# fsm.net
KiCad netlist of a schematic drawn in Altium Designer
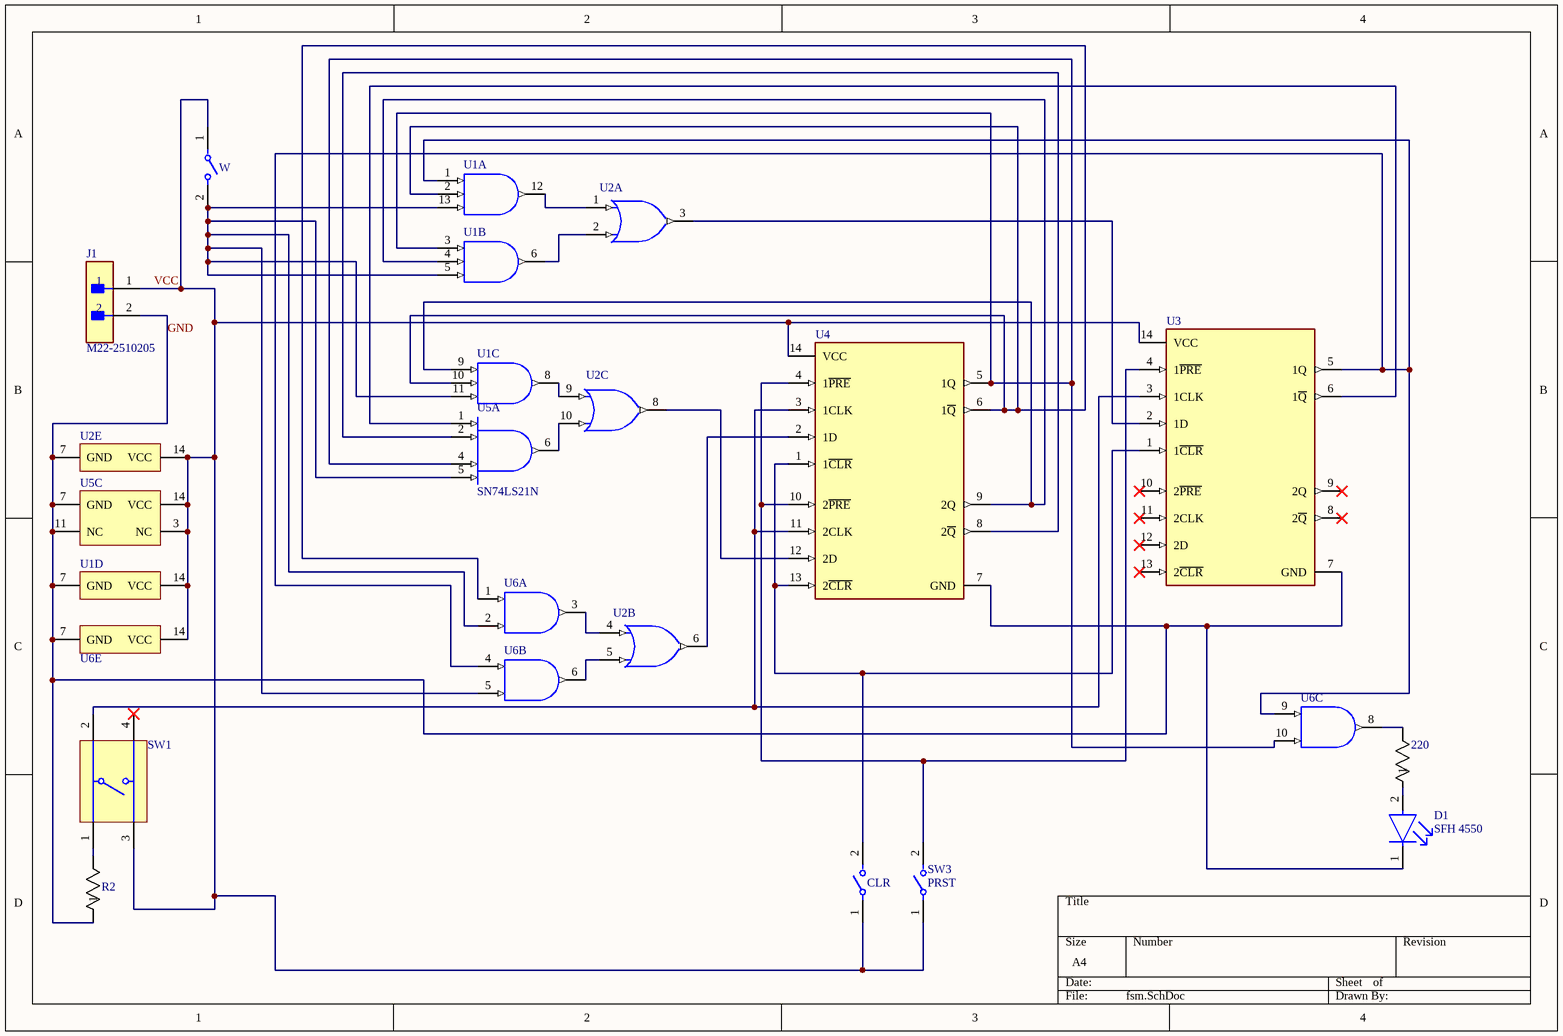
[diagram p0: fsm.SchDoc]

(export (version "E")
  (design (tool "Eeschema 10.0.6"))
  (components
    (comp (ref "220")
      (value "AC05000002200JAC00")
      (footprint "RES_AC05_VIS")
      (description "AC05000002200JAC00 Resistor, 220 Ohm, ± 5%, 5 W, Axial Leaded, Wirewound, General Purpose")
      (fields (field (name "TOLERANCE") "5%"))
      (libsource (lib "Altium Content Vault") (part "AC05000002200JAC00"))
    )
    (comp (ref "D1")
      (value "SFH 4550")
      (footprint "FP-SFH_4550-MFG")
      (description "EMITTER IR 860NM 100MA RADIAL")
      (fields
        (field (name "OCTOPART") "https://octopart.com/sfh+4550-osram+opto-55410894")
        (field (name "MANUFACTURER") "Osram Opto")
      )
      (libsource (lib "Altium Content Vault") (part "75a0115997dd6a71327e26aab64f6f8"))
    )
    (comp (ref "J1")
      (value "M22-2510205")
      (footprint "FP-M22-2510205-MFG")
      (description "CONN HEADER VERT 2POS 2MM")
      (fields
        (field (name "MANUFACTURER") "Harwin")
        (field (name "OCTOPART") "https://octopart.com/m22-2510205-harwin-2538221")
      )
      (libsource (lib "Altium Content Vault") (part "3bc925449376181038e59eaffc5286c"))
    )
    (comp (ref "R2")
      (value "AC03000001001JAC00")
      (footprint "RES_AC03_VIS")
      (description "AC03000001001JAC00 Resistor, 1 kOhm, ± 5%, 3 W, Axial Leaded, Wirewound, General Purpose")
      (fields (field (name "TOLERANCE") "5%"))
      (libsource (lib "Altium Content Vault") (part "AC03000001001JAC00"))
    )
    (comp (ref "SW1")
      (value "1825910-6")
      (footprint "TECO-1825910-6_V")
      (description "Tact Switch, SPST-NO, 0.05 A, -35 to 85 degC, 4-Pin THD, RoHS, Bulk")
      (fields (field (name "MANUFACTURER") "TE Connectivity"))
      (libsource (lib "Altium Content Vault") (part "SW-SPST-4_A"))
    )
    (comp (ref "SW2")
      (value "CLR")
      (footprint "FP-BD01-MFG")
      (description "SWITCH SLIDE DIP SPST 100MA 5V")
      (libsource (lib "Altium Content Vault") (part "bb27bde45df87f1f469753f287ef5ae"))
    )
    (comp (ref "SW3")
      (value "PRST")
      (footprint "FP-BD01-MFG")
      (description "SWITCH SLIDE DIP SPST 100MA 5V")
      (libsource (lib "Altium Content Vault") (part "bb27bde45df87f1f469753f287ef5ae"))
    )
    (comp (ref "U1")
      (value "SN74LS11N")
      (footprint "N0014A")
      (description "Triple 3-input positive-AND gates, N0014A, TUBE")
      (fields
        (field (name "MANUFACTURER") "Texas Instruments")
        (field (name "GENERIC PART NUMBER") "SN74LS11")
      )
      (libsource (lib "Altium Content Vault") (part "TI-AND-3-3IN-14"))
    )
    (comp (ref "U2")
      (value "SN74AHC32N")
      (footprint "N0014A")
      (description "Quadruple 2-Input Positive-OR Gates, N0014A, TUBE")
      (fields
        (field (name "MANUFACTURER") "Texas Instruments")
        (field (name "GENERIC PART NUMBER") "SN74AHC32")
      )
      (libsource (lib "Altium Content Vault") (part "TI-OR-4-2IN-14"))
    )
    (comp (ref "U3")
      (value "SN74HCT74N")
      (footprint "FP-N0014A-MFG")
      (description "IC FF D-TYPE DUAL 1BIT 14DIP")
      (libsource (lib "Altium Content Vault") (part "d9c658a62ce850adab6c7e3446338f7"))
    )
    (comp (ref "U4")
      (value "SN74HCT74N")
      (footprint "FP-N0014A-MFG")
      (description "IC FF D-TYPE DUAL 1BIT 14DIP")
      (libsource (lib "Altium Content Vault") (part "d9c658a62ce850adab6c7e3446338f7"))
    )
    (comp (ref "U5")
      (value "SN74LS21N")
      (footprint "N0014A")
      (description "Dual 4-input positive-AND gates, N0014A, TUBE")
      (fields
        (field (name "GENERIC PART NUMBER") "SN74LS21")
        (field (name "MANUFACTURER") "Texas Instruments")
      )
      (libsource (lib "") (part "TI-SNX4XXX21X-14_1"))
    )
    (comp (ref "U6")
      (value "SN74AC08N")
      (footprint "N0014A")
      (description "Quadruple 2-Input Positive-AND Gates, N0014A, TUBE")
      (fields
        (field (name "GENERIC PART NUMBER") "SN74AC08")
        (field (name "MANUFACTURER") "Texas Instruments")
      )
      (libsource (lib "Altium Content Vault") (part "TI-AND-4-2IN-14"))
    )
    (comp (ref "W")
      (value "BD01")
      (footprint "FP-BD01-MFG")
      (description "SWITCH SLIDE DIP SPST 100MA 5V")
      (libsource (lib "Altium Content Vault") (part "bb27bde45df87f1f469753f287ef5ae"))
    )
  )
  (nets
    (net (code "1") (name "/GND") (class "Default")
      (node (ref "D1") (pin "1") (pinfunction "C_1") (pintype "passive"))
      (node (ref "J1") (pin "2") (pinfunction "2_2") (pintype "passive"))
      (node (ref "R2") (pin "1") (pinfunction "1_1") (pintype "passive"))
      (node (ref "U1") (pin "7") (pinfunction "GND_7") (pintype "power_in"))
      (node (ref "U2") (pin "7") (pinfunction "GND_7") (pintype "power_in"))
      (node (ref "U3") (pin "7") (pinfunction "GND_7") (pintype "power_in"))
      (node (ref "U4") (pin "7") (pinfunction "GND_7") (pintype "power_in"))
      (node (ref "U5") (pin "11") (pinfunction "NC_11") (pintype "passive"))
      (node (ref "U5") (pin "7") (pinfunction "GND_7") (pintype "power_in"))
      (node (ref "U6") (pin "7") (pinfunction "GND_7") (pintype "power_in"))
    )
    (net (code "2") (name "/VCC") (class "Default")
      (node (ref "J1") (pin "1") (pinfunction "1_1") (pintype "passive"))
      (node (ref "SW1") (pin "3") (pinfunction "3_3") (pintype "passive"))
      (node (ref "SW2") (pin "1") (pinfunction "1_1") (pintype "passive"))
      (node (ref "SW3") (pin "1") (pinfunction "1_1") (pintype "passive"))
      (node (ref "U1") (pin "14") (pinfunction "VCC_14") (pintype "power_in"))
      (node (ref "U2") (pin "14") (pinfunction "VCC_14") (pintype "power_in"))
      (node (ref "U3") (pin "14") (pinfunction "VCC_14") (pintype "power_in"))
      (node (ref "U4") (pin "14") (pinfunction "VCC_14") (pintype "power_in"))
      (node (ref "U5") (pin "14") (pinfunction "VCC_14") (pintype "power_in"))
      (node (ref "U5") (pin "3") (pinfunction "NC_3") (pintype "passive"))
      (node (ref "U6") (pin "14") (pinfunction "VCC_14") (pintype "power_in"))
      (node (ref "W") (pin "1") (pinfunction "1_1") (pintype "passive"))
    )
    (net (code "3") (name "Net-(D1-A)") (class "Default")
      (node (ref "220") (pin "1") (pinfunction "1_1") (pintype "passive"))
      (node (ref "D1") (pin "2") (pinfunction "A_2") (pintype "passive"))
    )
    (net (code "4") (name "Net-(R2-Pad2)") (class "Default")
      (node (ref "R2") (pin "2") (pinfunction "2_2") (pintype "passive"))
      (node (ref "SW1") (pin "1") (pinfunction "1_1") (pintype "passive"))
    )
    (net (code "5") (name "Net-(U1A-1A)") (class "Default")
      (node (ref "U1") (pin "1") (pinfunction "1A_1") (pintype "input"))
      (node (ref "U3") (pin "5") (pinfunction "1Q_5") (pintype "output"))
      (node (ref "U6") (pin "4") (pinfunction "2A_4") (pintype "input"))
      (node (ref "U6") (pin "9") (pinfunction "3A_9") (pintype "input"))
    )
    (net (code "6") (name "Net-(U1A-1B)") (class "Default")
      (node (ref "U1") (pin "10") (pinfunction "3B_10") (pintype "input"))
      (node (ref "U1") (pin "2") (pinfunction "1B_2") (pintype "input"))
      (node (ref "U4") (pin "6") (pinfunction "1~{Q}_6") (pintype "output"))
      (node (ref "U6") (pin "1") (pinfunction "1A_1") (pintype "input"))
    )
    (net (code "7") (name "Net-(U1A-1C)") (class "Default")
      (node (ref "U1") (pin "11") (pinfunction "3C_11") (pintype "input"))
      (node (ref "U1") (pin "13") (pinfunction "1C_13") (pintype "input"))
      (node (ref "U1") (pin "5") (pinfunction "2C_5") (pintype "input"))
      (node (ref "U5") (pin "5") (pinfunction "1D_5") (pintype "input"))
      (node (ref "U6") (pin "2") (pinfunction "1B_2") (pintype "input"))
      (node (ref "U6") (pin "5") (pinfunction "2B_5") (pintype "input"))
      (node (ref "W") (pin "2") (pinfunction "2_2") (pintype "passive"))
    )
    (net (code "8") (name "Net-(U1A-1Y)") (class "Default")
      (node (ref "U1") (pin "12") (pinfunction "1Y_12") (pintype "output"))
      (node (ref "U2") (pin "1") (pinfunction "1A_1") (pintype "input"))
    )
    (net (code "9") (name "Net-(U1B-2A)") (class "Default")
      (node (ref "U1") (pin "3") (pinfunction "2A_3") (pintype "input"))
      (node (ref "U4") (pin "5") (pinfunction "1Q_5") (pintype "output"))
      (node (ref "U5") (pin "4") (pinfunction "1C_4") (pintype "input"))
      (node (ref "U6") (pin "10") (pinfunction "3B_10") (pintype "input"))
    )
    (net (code "10") (name "Net-(U1B-2B)") (class "Default")
      (node (ref "U1") (pin "4") (pinfunction "2B_4") (pintype "input"))
      (node (ref "U1") (pin "9") (pinfunction "3A_9") (pintype "input"))
      (node (ref "U4") (pin "9") (pinfunction "2Q_9") (pintype "output"))
    )
    (net (code "11") (name "Net-(U1B-2Y)") (class "Default")
      (node (ref "U1") (pin "6") (pinfunction "2Y_6") (pintype "output"))
      (node (ref "U2") (pin "2") (pinfunction "1B_2") (pintype "input"))
    )
    (net (code "12") (name "Net-(U1C-3Y)") (class "Default")
      (node (ref "U1") (pin "8") (pinfunction "3Y_8") (pintype "output"))
      (node (ref "U2") (pin "9") (pinfunction "3A_9") (pintype "input"))
    )
    (net (code "13") (name "Net-(U2A-1Y)") (class "Default")
      (node (ref "U2") (pin "3") (pinfunction "1Y_3") (pintype "output"))
      (node (ref "U3") (pin "2") (pinfunction "1D_2") (pintype "input"))
    )
    (net (code "14") (name "Net-(U2B-2A)") (class "Default")
      (node (ref "U2") (pin "4") (pinfunction "2A_4") (pintype "input"))
      (node (ref "U6") (pin "3") (pinfunction "1Y_3") (pintype "output"))
    )
    (net (code "15") (name "Net-(U2B-2B)") (class "Default")
      (node (ref "U2") (pin "5") (pinfunction "2B_5") (pintype "input"))
      (node (ref "U6") (pin "6") (pinfunction "2Y_6") (pintype "output"))
    )
    (net (code "16") (name "Net-(U2B-2Y)") (class "Default")
      (node (ref "U2") (pin "6") (pinfunction "2Y_6") (pintype "output"))
      (node (ref "U4") (pin "2") (pinfunction "1D_2") (pintype "input"))
    )
    (net (code "17") (name "Net-(U2C-3B)") (class "Default")
      (node (ref "U2") (pin "10") (pinfunction "3B_10") (pintype "input"))
      (node (ref "U5") (pin "6") (pinfunction "1Y_6") (pintype "output"))
    )
    (net (code "18") (name "Net-(U2C-3Y)") (class "Default")
      (node (ref "U2") (pin "8") (pinfunction "3Y_8") (pintype "output"))
      (node (ref "U4") (pin "12") (pinfunction "2D_12") (pintype "input"))
    )
    (net (code "19") (name "Net-(U3-1CLK)") (class "Default")
      (node (ref "SW1") (pin "2") (pinfunction "2_2") (pintype "passive"))
      (node (ref "U3") (pin "3") (pinfunction "1CLK_3") (pintype "input"))
      (node (ref "U4") (pin "11") (pinfunction "2CLK_11") (pintype "input"))
      (node (ref "U4") (pin "3") (pinfunction "1CLK_3") (pintype "input"))
    )
    (net (code "20") (name "Net-(U3-1~{CLR})") (class "Default")
      (node (ref "SW2") (pin "2") (pinfunction "2_2") (pintype "passive"))
      (node (ref "U3") (pin "1") (pinfunction "1~{CLR}_1") (pintype "input"))
      (node (ref "U4") (pin "1") (pinfunction "1~{CLR}_1") (pintype "input"))
      (node (ref "U4") (pin "13") (pinfunction "2~{CLR}_13") (pintype "input"))
    )
    (net (code "21") (name "Net-(U3-1~{PRE})") (class "Default")
      (node (ref "SW3") (pin "2") (pinfunction "2_2") (pintype "passive"))
      (node (ref "U3") (pin "4") (pinfunction "1~{PRE}_4") (pintype "input"))
      (node (ref "U4") (pin "10") (pinfunction "2~{PRE}_10") (pintype "input"))
      (node (ref "U4") (pin "4") (pinfunction "1~{PRE}_4") (pintype "input"))
    )
    (net (code "22") (name "Net-(U3-1~{Q})") (class "Default")
      (node (ref "U3") (pin "6") (pinfunction "1~{Q}_6") (pintype "output"))
      (node (ref "U5") (pin "1") (pinfunction "1A_1") (pintype "input"))
    )
    (net (code "23") (name "Net-(U4-2~{Q})") (class "Default")
      (node (ref "U4") (pin "8") (pinfunction "2~{Q}_8") (pintype "output"))
      (node (ref "U5") (pin "2") (pinfunction "1B_2") (pintype "input"))
    )
    (net (code "24") (name "Net-(U6C-3Y)") (class "Default")
      (node (ref "220") (pin "2") (pinfunction "2_2") (pintype "passive"))
      (node (ref "U6") (pin "8") (pinfunction "3Y_8") (pintype "output"))
    )
    (net (code "25") (name "unconnected-(SW1-Pad4)") (class "Default")
      (node (ref "SW1") (pin "4") (pinfunction "4_4") (pintype "passive+no_connect"))
    )
    (net (code "26") (name "unconnected-(U3-2CLK-Pad11)") (class "Default")
      (node (ref "U3") (pin "11") (pinfunction "2CLK_11") (pintype "input+no_connect"))
    )
    (net (code "27") (name "unconnected-(U3-2D-Pad12)") (class "Default")
      (node (ref "U3") (pin "12") (pinfunction "2D_12") (pintype "input+no_connect"))
    )
    (net (code "28") (name "unconnected-(U3-2Q-Pad9)") (class "Default")
      (node (ref "U3") (pin "9") (pinfunction "2Q_9") (pintype "output+no_connect"))
    )
    (net (code "29") (name "unconnected-(U3-2~{CLR}-Pad13)") (class "Default")
      (node (ref "U3") (pin "13") (pinfunction "2~{CLR}_13") (pintype "input+no_connect"))
    )
    (net (code "30") (name "unconnected-(U3-2~{PRE}-Pad10)") (class "Default")
      (node (ref "U3") (pin "10") (pinfunction "2~{PRE}_10") (pintype "input+no_connect"))
    )
    (net (code "31") (name "unconnected-(U3-2~{Q}-Pad8)") (class "Default")
      (node (ref "U3") (pin "8") (pinfunction "2~{Q}_8") (pintype "output+no_connect"))
    )
  )
)
